# breadboard-long-with-header.net
KiCad netlist of a schematic drawn in EAGLE
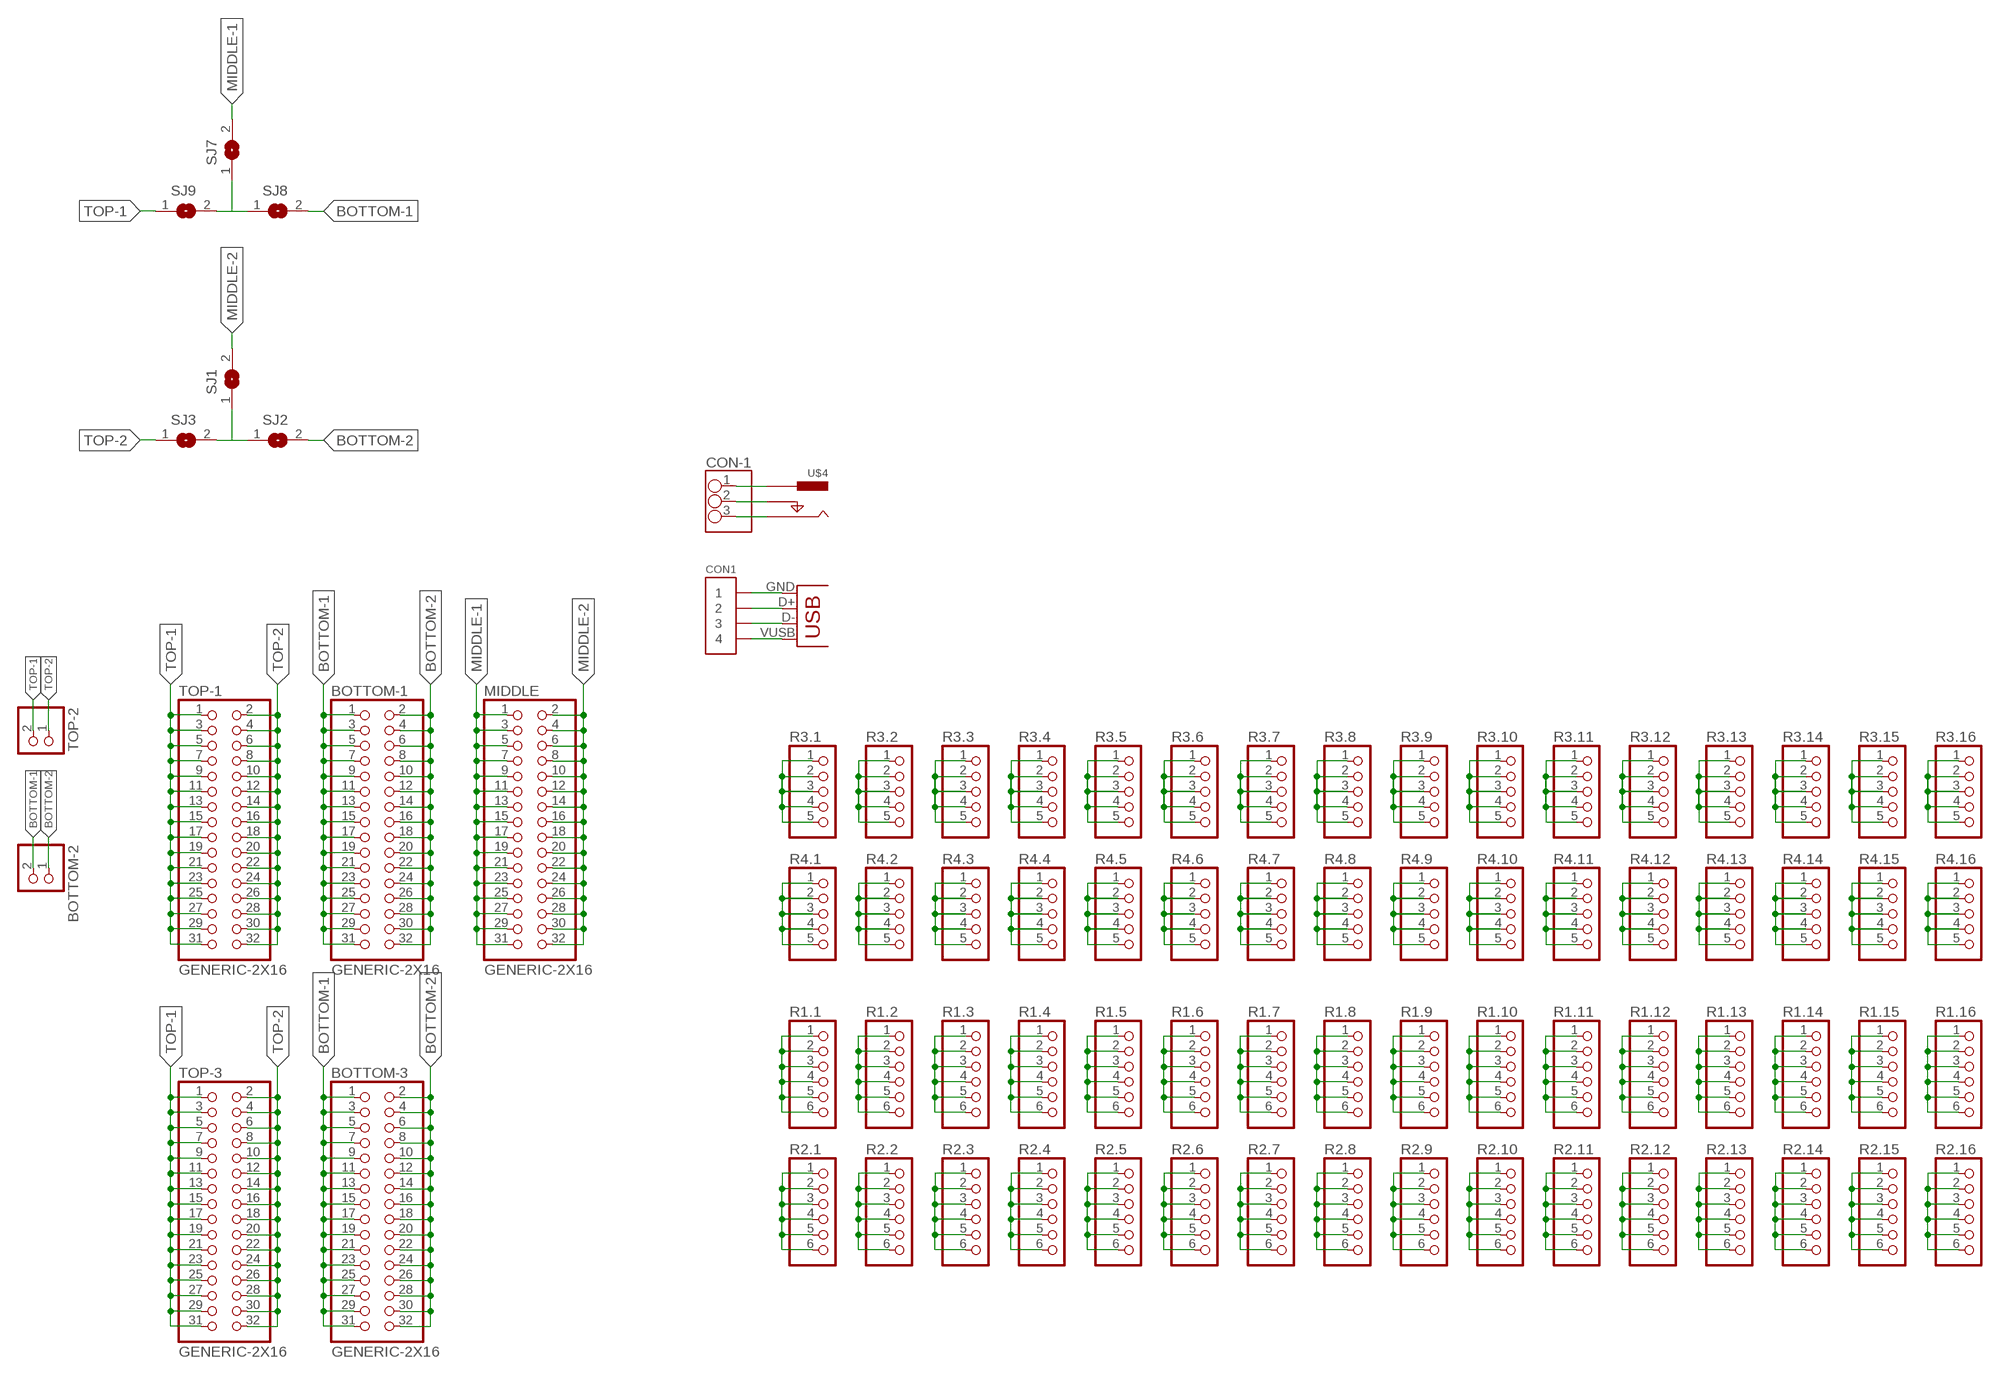
[diagram p0: schematic, sheet 1]

(export (version "E")
  (design (tool "Eeschema 10.0.6"))
  (components
    (comp (ref "BOTTOM-1")
      (value "GENERIC-2X16")
      (footprint "eagle-import:PINHEADER-100MIL-2X16-NOSILK")
      (libsource (lib "eagle-import") (part "GENERIC-2X16"))
    )
    (comp (ref "BOTTOM-2")
      (value "GENERIC-1X2")
      (footprint "eagle-import:PINHEADER-100MIL-1X2-NOSILK")
      (libsource (lib "eagle-import") (part "GENERIC-1X2"))
    )
    (comp (ref "BOTTOM-3")
      (value "GENERIC-2X16")
      (footprint "eagle-import:PINHEADER-100MIL-2X16-NOSILK")
      (libsource (lib "eagle-import") (part "GENERIC-2X16"))
    )
    (comp (ref "CON-1")
      (value "GENERIC-1X3")
      (footprint "eagle-import:PINHEADER-100MIL-1X3-NOSILK")
      (libsource (lib "eagle-import") (part "GENERIC-1X3"))
    )
    (comp (ref "CON1")
      (value "GENERIC-1X4STRAIGHT")
      (footprint "eagle-import:PINHEADER-100MIL-1X4-NOSILK")
      (libsource (lib "eagle-import") (part "GENERIC-1X4STRAIGHT"))
    )
    (comp (ref "MIDDLE")
      (value "GENERIC-2X16")
      (footprint "eagle-import:PINHEADER-100MIL-2X16-NOSILK")
      (libsource (lib "eagle-import") (part "GENERIC-2X16"))
    )
    (comp (ref "R1.1")
      (value "GENERIC-1X6")
      (footprint "eagle-import:PINHEADER-100MIL-1X6-NOSILK")
      (libsource (lib "eagle-import") (part "GENERIC-1X6"))
    )
    (comp (ref "R1.2")
      (value "GENERIC-1X6")
      (footprint "eagle-import:PINHEADER-100MIL-1X6-NOSILK")
      (libsource (lib "eagle-import") (part "GENERIC-1X6"))
    )
    (comp (ref "R1.3")
      (value "GENERIC-1X6")
      (footprint "eagle-import:PINHEADER-100MIL-1X6-NOSILK")
      (libsource (lib "eagle-import") (part "GENERIC-1X6"))
    )
    (comp (ref "R1.4")
      (value "GENERIC-1X6")
      (footprint "eagle-import:PINHEADER-100MIL-1X6-NOSILK")
      (libsource (lib "eagle-import") (part "GENERIC-1X6"))
    )
    (comp (ref "R1.5")
      (value "GENERIC-1X6")
      (footprint "eagle-import:PINHEADER-100MIL-1X6-NOSILK")
      (libsource (lib "eagle-import") (part "GENERIC-1X6"))
    )
    (comp (ref "R1.6")
      (value "GENERIC-1X6")
      (footprint "eagle-import:PINHEADER-100MIL-1X6-NOSILK")
      (libsource (lib "eagle-import") (part "GENERIC-1X6"))
    )
    (comp (ref "R1.7")
      (value "GENERIC-1X6")
      (footprint "eagle-import:PINHEADER-100MIL-1X6-NOSILK")
      (libsource (lib "eagle-import") (part "GENERIC-1X6"))
    )
    (comp (ref "R1.8")
      (value "GENERIC-1X6")
      (footprint "eagle-import:PINHEADER-100MIL-1X6-NOSILK")
      (libsource (lib "eagle-import") (part "GENERIC-1X6"))
    )
    (comp (ref "R1.9")
      (value "GENERIC-1X6")
      (footprint "eagle-import:PINHEADER-100MIL-1X6-NOSILK")
      (libsource (lib "eagle-import") (part "GENERIC-1X6"))
    )
    (comp (ref "R1.10")
      (value "GENERIC-1X6")
      (footprint "eagle-import:PINHEADER-100MIL-1X6-NOSILK")
      (libsource (lib "eagle-import") (part "GENERIC-1X6"))
    )
    (comp (ref "R1.11")
      (value "GENERIC-1X6")
      (footprint "eagle-import:PINHEADER-100MIL-1X6-NOSILK")
      (libsource (lib "eagle-import") (part "GENERIC-1X6"))
    )
    (comp (ref "R1.12")
      (value "GENERIC-1X6")
      (footprint "eagle-import:PINHEADER-100MIL-1X6-NOSILK")
      (libsource (lib "eagle-import") (part "GENERIC-1X6"))
    )
    (comp (ref "R1.13")
      (value "GENERIC-1X6")
      (footprint "eagle-import:PINHEADER-100MIL-1X6-NOSILK")
      (libsource (lib "eagle-import") (part "GENERIC-1X6"))
    )
    (comp (ref "R1.14")
      (value "GENERIC-1X6")
      (footprint "eagle-import:PINHEADER-100MIL-1X6-NOSILK")
      (libsource (lib "eagle-import") (part "GENERIC-1X6"))
    )
    (comp (ref "R1.15")
      (value "GENERIC-1X6")
      (footprint "eagle-import:PINHEADER-100MIL-1X6-NOSILK")
      (libsource (lib "eagle-import") (part "GENERIC-1X6"))
    )
    (comp (ref "R1.16")
      (value "GENERIC-1X6")
      (footprint "eagle-import:PINHEADER-100MIL-1X6-NOSILK")
      (libsource (lib "eagle-import") (part "GENERIC-1X6"))
    )
    (comp (ref "R2.1")
      (value "GENERIC-1X6")
      (footprint "eagle-import:PINHEADER-100MIL-1X6-NOSILK")
      (libsource (lib "eagle-import") (part "GENERIC-1X6"))
    )
    (comp (ref "R2.2")
      (value "GENERIC-1X6")
      (footprint "eagle-import:PINHEADER-100MIL-1X6-NOSILK")
      (libsource (lib "eagle-import") (part "GENERIC-1X6"))
    )
    (comp (ref "R2.3")
      (value "GENERIC-1X6")
      (footprint "eagle-import:PINHEADER-100MIL-1X6-NOSILK")
      (libsource (lib "eagle-import") (part "GENERIC-1X6"))
    )
    (comp (ref "R2.4")
      (value "GENERIC-1X6")
      (footprint "eagle-import:PINHEADER-100MIL-1X6-NOSILK")
      (libsource (lib "eagle-import") (part "GENERIC-1X6"))
    )
    (comp (ref "R2.5")
      (value "GENERIC-1X6")
      (footprint "eagle-import:PINHEADER-100MIL-1X6-NOSILK")
      (libsource (lib "eagle-import") (part "GENERIC-1X6"))
    )
    (comp (ref "R2.6")
      (value "GENERIC-1X6")
      (footprint "eagle-import:PINHEADER-100MIL-1X6-NOSILK")
      (libsource (lib "eagle-import") (part "GENERIC-1X6"))
    )
    (comp (ref "R2.7")
      (value "GENERIC-1X6")
      (footprint "eagle-import:PINHEADER-100MIL-1X6-NOSILK")
      (libsource (lib "eagle-import") (part "GENERIC-1X6"))
    )
    (comp (ref "R2.8")
      (value "GENERIC-1X6")
      (footprint "eagle-import:PINHEADER-100MIL-1X6-NOSILK")
      (libsource (lib "eagle-import") (part "GENERIC-1X6"))
    )
    (comp (ref "R2.9")
      (value "GENERIC-1X6")
      (footprint "eagle-import:PINHEADER-100MIL-1X6-NOSILK")
      (libsource (lib "eagle-import") (part "GENERIC-1X6"))
    )
    (comp (ref "R2.10")
      (value "GENERIC-1X6")
      (footprint "eagle-import:PINHEADER-100MIL-1X6-NOSILK")
      (libsource (lib "eagle-import") (part "GENERIC-1X6"))
    )
    (comp (ref "R2.11")
      (value "GENERIC-1X6")
      (footprint "eagle-import:PINHEADER-100MIL-1X6-NOSILK")
      (libsource (lib "eagle-import") (part "GENERIC-1X6"))
    )
    (comp (ref "R2.12")
      (value "GENERIC-1X6")
      (footprint "eagle-import:PINHEADER-100MIL-1X6-NOSILK")
      (libsource (lib "eagle-import") (part "GENERIC-1X6"))
    )
    (comp (ref "R2.13")
      (value "GENERIC-1X6")
      (footprint "eagle-import:PINHEADER-100MIL-1X6-NOSILK")
      (libsource (lib "eagle-import") (part "GENERIC-1X6"))
    )
    (comp (ref "R2.14")
      (value "GENERIC-1X6")
      (footprint "eagle-import:PINHEADER-100MIL-1X6-NOSILK")
      (libsource (lib "eagle-import") (part "GENERIC-1X6"))
    )
    (comp (ref "R2.15")
      (value "GENERIC-1X6")
      (footprint "eagle-import:PINHEADER-100MIL-1X6-NOSILK")
      (libsource (lib "eagle-import") (part "GENERIC-1X6"))
    )
    (comp (ref "R2.16")
      (value "GENERIC-1X6")
      (footprint "eagle-import:PINHEADER-100MIL-1X6-NOSILK")
      (libsource (lib "eagle-import") (part "GENERIC-1X6"))
    )
    (comp (ref "R3.1")
      (value "GENERIC-1X5")
      (footprint "eagle-import:PINHEADER-100MIL-1X5-NOSILK")
      (libsource (lib "eagle-import") (part "GENERIC-1X5"))
    )
    (comp (ref "R3.2")
      (value "GENERIC-1X5")
      (footprint "eagle-import:PINHEADER-100MIL-1X5-NOSILK")
      (libsource (lib "eagle-import") (part "GENERIC-1X5"))
    )
    (comp (ref "R3.3")
      (value "GENERIC-1X5")
      (footprint "eagle-import:PINHEADER-100MIL-1X5-NOSILK")
      (libsource (lib "eagle-import") (part "GENERIC-1X5"))
    )
    (comp (ref "R3.4")
      (value "GENERIC-1X5")
      (footprint "eagle-import:PINHEADER-100MIL-1X5-NOSILK")
      (libsource (lib "eagle-import") (part "GENERIC-1X5"))
    )
    (comp (ref "R3.5")
      (value "GENERIC-1X5")
      (footprint "eagle-import:PINHEADER-100MIL-1X5-NOSILK")
      (libsource (lib "eagle-import") (part "GENERIC-1X5"))
    )
    (comp (ref "R3.6")
      (value "GENERIC-1X5")
      (footprint "eagle-import:PINHEADER-100MIL-1X5-NOSILK")
      (libsource (lib "eagle-import") (part "GENERIC-1X5"))
    )
    (comp (ref "R3.7")
      (value "GENERIC-1X5")
      (footprint "eagle-import:PINHEADER-100MIL-1X5-NOSILK")
      (libsource (lib "eagle-import") (part "GENERIC-1X5"))
    )
    (comp (ref "R3.8")
      (value "GENERIC-1X5")
      (footprint "eagle-import:PINHEADER-100MIL-1X5-NOSILK")
      (libsource (lib "eagle-import") (part "GENERIC-1X5"))
    )
    (comp (ref "R3.9")
      (value "GENERIC-1X5")
      (footprint "eagle-import:PINHEADER-100MIL-1X5-NOSILK")
      (libsource (lib "eagle-import") (part "GENERIC-1X5"))
    )
    (comp (ref "R3.10")
      (value "GENERIC-1X5")
      (footprint "eagle-import:PINHEADER-100MIL-1X5-NOSILK")
      (libsource (lib "eagle-import") (part "GENERIC-1X5"))
    )
    (comp (ref "R3.11")
      (value "GENERIC-1X5")
      (footprint "eagle-import:PINHEADER-100MIL-1X5-NOSILK")
      (libsource (lib "eagle-import") (part "GENERIC-1X5"))
    )
    (comp (ref "R3.12")
      (value "GENERIC-1X5")
      (footprint "eagle-import:PINHEADER-100MIL-1X5-NOSILK")
      (libsource (lib "eagle-import") (part "GENERIC-1X5"))
    )
    (comp (ref "R3.13")
      (value "GENERIC-1X5")
      (footprint "eagle-import:PINHEADER-100MIL-1X5-NOSILK")
      (libsource (lib "eagle-import") (part "GENERIC-1X5"))
    )
    (comp (ref "R3.14")
      (value "GENERIC-1X5")
      (footprint "eagle-import:PINHEADER-100MIL-1X5-NOSILK")
      (libsource (lib "eagle-import") (part "GENERIC-1X5"))
    )
    (comp (ref "R3.15")
      (value "GENERIC-1X5")
      (footprint "eagle-import:PINHEADER-100MIL-1X5-NOSILK")
      (libsource (lib "eagle-import") (part "GENERIC-1X5"))
    )
    (comp (ref "R3.16")
      (value "GENERIC-1X5")
      (footprint "eagle-import:PINHEADER-100MIL-1X5-NOSILK")
      (libsource (lib "eagle-import") (part "GENERIC-1X5"))
    )
    (comp (ref "R4.1")
      (value "GENERIC-1X5")
      (footprint "eagle-import:PINHEADER-100MIL-1X5-NOSILK")
      (libsource (lib "eagle-import") (part "GENERIC-1X5"))
    )
    (comp (ref "R4.2")
      (value "GENERIC-1X5")
      (footprint "eagle-import:PINHEADER-100MIL-1X5-NOSILK")
      (libsource (lib "eagle-import") (part "GENERIC-1X5"))
    )
    (comp (ref "R4.3")
      (value "GENERIC-1X5")
      (footprint "eagle-import:PINHEADER-100MIL-1X5-NOSILK")
      (libsource (lib "eagle-import") (part "GENERIC-1X5"))
    )
    (comp (ref "R4.4")
      (value "GENERIC-1X5")
      (footprint "eagle-import:PINHEADER-100MIL-1X5-NOSILK")
      (libsource (lib "eagle-import") (part "GENERIC-1X5"))
    )
    (comp (ref "R4.5")
      (value "GENERIC-1X5")
      (footprint "eagle-import:PINHEADER-100MIL-1X5-NOSILK")
      (libsource (lib "eagle-import") (part "GENERIC-1X5"))
    )
    (comp (ref "R4.6")
      (value "GENERIC-1X5")
      (footprint "eagle-import:PINHEADER-100MIL-1X5-NOSILK")
      (libsource (lib "eagle-import") (part "GENERIC-1X5"))
    )
    (comp (ref "R4.7")
      (value "GENERIC-1X5")
      (footprint "eagle-import:PINHEADER-100MIL-1X5-NOSILK")
      (libsource (lib "eagle-import") (part "GENERIC-1X5"))
    )
    (comp (ref "R4.8")
      (value "GENERIC-1X5")
      (footprint "eagle-import:PINHEADER-100MIL-1X5-NOSILK")
      (libsource (lib "eagle-import") (part "GENERIC-1X5"))
    )
    (comp (ref "R4.9")
      (value "GENERIC-1X5")
      (footprint "eagle-import:PINHEADER-100MIL-1X5-NOSILK")
      (libsource (lib "eagle-import") (part "GENERIC-1X5"))
    )
    (comp (ref "R4.10")
      (value "GENERIC-1X5")
      (footprint "eagle-import:PINHEADER-100MIL-1X5-NOSILK")
      (libsource (lib "eagle-import") (part "GENERIC-1X5"))
    )
    (comp (ref "R4.11")
      (value "GENERIC-1X5")
      (footprint "eagle-import:PINHEADER-100MIL-1X5-NOSILK")
      (libsource (lib "eagle-import") (part "GENERIC-1X5"))
    )
    (comp (ref "R4.12")
      (value "GENERIC-1X5")
      (footprint "eagle-import:PINHEADER-100MIL-1X5-NOSILK")
      (libsource (lib "eagle-import") (part "GENERIC-1X5"))
    )
    (comp (ref "R4.13")
      (value "GENERIC-1X5")
      (footprint "eagle-import:PINHEADER-100MIL-1X5-NOSILK")
      (libsource (lib "eagle-import") (part "GENERIC-1X5"))
    )
    (comp (ref "R4.14")
      (value "GENERIC-1X5")
      (footprint "eagle-import:PINHEADER-100MIL-1X5-NOSILK")
      (libsource (lib "eagle-import") (part "GENERIC-1X5"))
    )
    (comp (ref "R4.15")
      (value "GENERIC-1X5")
      (footprint "eagle-import:PINHEADER-100MIL-1X5-NOSILK")
      (libsource (lib "eagle-import") (part "GENERIC-1X5"))
    )
    (comp (ref "R4.16")
      (value "GENERIC-1X5")
      (footprint "eagle-import:PINHEADER-100MIL-1X5-NOSILK")
      (libsource (lib "eagle-import") (part "GENERIC-1X5"))
    )
    (comp (ref "SJ1") (value "SJ") (footprint "eagle-import:SJ") (libsource (lib "eagle-import") (part "SJ")))
    (comp (ref "SJ2") (value "SJ") (footprint "eagle-import:SJ") (libsource (lib "eagle-import") (part "SJ")))
    (comp (ref "SJ3") (value "SJ") (footprint "eagle-import:SJ") (libsource (lib "eagle-import") (part "SJ")))
    (comp (ref "SJ7") (value "SJ") (footprint "eagle-import:SJ") (libsource (lib "eagle-import") (part "SJ")))
    (comp (ref "SJ8") (value "SJ") (footprint "eagle-import:SJ") (libsource (lib "eagle-import") (part "SJ")))
    (comp (ref "SJ9") (value "SJ") (footprint "eagle-import:SJ") (libsource (lib "eagle-import") (part "SJ")))
    (comp (ref "TOP-1")
      (value "GENERIC-2X16")
      (footprint "eagle-import:PINHEADER-100MIL-2X16-NOSILK")
      (libsource (lib "eagle-import") (part "GENERIC-2X16"))
    )
    (comp (ref "TOP-2")
      (value "GENERIC-1X2")
      (footprint "eagle-import:PINHEADER-100MIL-1X2-NOSILK")
      (libsource (lib "eagle-import") (part "GENERIC-1X2"))
    )
    (comp (ref "TOP-3")
      (value "GENERIC-2X16")
      (footprint "eagle-import:PINHEADER-100MIL-2X16-NOSILK")
      (libsource (lib "eagle-import") (part "GENERIC-2X16"))
    )
    (comp (ref "U$3")
      (value "USBMINI-HAND")
      (footprint "eagle-import:USB-MINI-B-HAND_EXTRA_LONG")
      (libsource (lib "eagle-import") (part "USBMINI-HAND"))
    )
    (comp (ref "U$4")
      (value "POWER-BARREL_JACKEBAY")
      (footprint "eagle-import:POWER-BARREL-2MM1-EBAY")
      (libsource (lib "eagle-import") (part "POWER-BARREL_JACKEBAY"))
    )
  )
  (nets
    (net (code "1") (name "BOTTOM-1") (class "Default")
      (node (ref "BOTTOM-1") (pin "1") (pinfunction "1_1") (pintype "passive"))
      (node (ref "BOTTOM-1") (pin "11") (pinfunction "11_11") (pintype "passive"))
      (node (ref "BOTTOM-1") (pin "13") (pinfunction "13_13") (pintype "passive"))
      (node (ref "BOTTOM-1") (pin "15") (pinfunction "15_15") (pintype "passive"))
      (node (ref "BOTTOM-1") (pin "17") (pinfunction "17_17") (pintype "passive"))
      (node (ref "BOTTOM-1") (pin "19") (pinfunction "19_19") (pintype "passive"))
      (node (ref "BOTTOM-1") (pin "21") (pinfunction "21_21") (pintype "passive"))
      (node (ref "BOTTOM-1") (pin "23") (pinfunction "23_23") (pintype "passive"))
      (node (ref "BOTTOM-1") (pin "25") (pinfunction "25_25") (pintype "passive"))
      (node (ref "BOTTOM-1") (pin "27") (pinfunction "27_27") (pintype "passive"))
      (node (ref "BOTTOM-1") (pin "29") (pinfunction "29_29") (pintype "passive"))
      (node (ref "BOTTOM-1") (pin "3") (pinfunction "3_3") (pintype "passive"))
      (node (ref "BOTTOM-1") (pin "31") (pinfunction "31_31") (pintype "passive"))
      (node (ref "BOTTOM-1") (pin "5") (pinfunction "5_5") (pintype "passive"))
      (node (ref "BOTTOM-1") (pin "7") (pinfunction "7_7") (pintype "passive"))
      (node (ref "BOTTOM-1") (pin "9") (pinfunction "9_9") (pintype "passive"))
      (node (ref "BOTTOM-2") (pin "2") (pinfunction "2_2") (pintype "passive"))
      (node (ref "BOTTOM-3") (pin "1") (pinfunction "1_1") (pintype "passive"))
      (node (ref "BOTTOM-3") (pin "11") (pinfunction "11_11") (pintype "passive"))
      (node (ref "BOTTOM-3") (pin "13") (pinfunction "13_13") (pintype "passive"))
      (node (ref "BOTTOM-3") (pin "15") (pinfunction "15_15") (pintype "passive"))
      (node (ref "BOTTOM-3") (pin "17") (pinfunction "17_17") (pintype "passive"))
      (node (ref "BOTTOM-3") (pin "19") (pinfunction "19_19") (pintype "passive"))
      (node (ref "BOTTOM-3") (pin "21") (pinfunction "21_21") (pintype "passive"))
      (node (ref "BOTTOM-3") (pin "23") (pinfunction "23_23") (pintype "passive"))
      (node (ref "BOTTOM-3") (pin "25") (pinfunction "25_25") (pintype "passive"))
      (node (ref "BOTTOM-3") (pin "27") (pinfunction "27_27") (pintype "passive"))
      (node (ref "BOTTOM-3") (pin "29") (pinfunction "29_29") (pintype "passive"))
      (node (ref "BOTTOM-3") (pin "3") (pinfunction "3_3") (pintype "passive"))
      (node (ref "BOTTOM-3") (pin "31") (pinfunction "31_31") (pintype "passive"))
      (node (ref "BOTTOM-3") (pin "5") (pinfunction "5_5") (pintype "passive"))
      (node (ref "BOTTOM-3") (pin "7") (pinfunction "7_7") (pintype "passive"))
      (node (ref "BOTTOM-3") (pin "9") (pinfunction "9_9") (pintype "passive"))
      (node (ref "SJ8") (pin "2") (pinfunction "2_2") (pintype "passive"))
    )
    (net (code "2") (name "BOTTOM-2") (class "Default")
      (node (ref "BOTTOM-1") (pin "10") (pinfunction "10_10") (pintype "passive"))
      (node (ref "BOTTOM-1") (pin "12") (pinfunction "12_12") (pintype "passive"))
      (node (ref "BOTTOM-1") (pin "14") (pinfunction "14_14") (pintype "passive"))
      (node (ref "BOTTOM-1") (pin "16") (pinfunction "16_16") (pintype "passive"))
      (node (ref "BOTTOM-1") (pin "18") (pinfunction "18_18") (pintype "passive"))
      (node (ref "BOTTOM-1") (pin "2") (pinfunction "2_2") (pintype "passive"))
      (node (ref "BOTTOM-1") (pin "20") (pinfunction "20_20") (pintype "passive"))
      (node (ref "BOTTOM-1") (pin "22") (pinfunction "22_22") (pintype "passive"))
      (node (ref "BOTTOM-1") (pin "24") (pinfunction "24_24") (pintype "passive"))
      (node (ref "BOTTOM-1") (pin "26") (pinfunction "26_26") (pintype "passive"))
      (node (ref "BOTTOM-1") (pin "28") (pinfunction "28_28") (pintype "passive"))
      (node (ref "BOTTOM-1") (pin "30") (pinfunction "30_30") (pintype "passive"))
      (node (ref "BOTTOM-1") (pin "32") (pinfunction "32_32") (pintype "passive"))
      (node (ref "BOTTOM-1") (pin "4") (pinfunction "4_4") (pintype "passive"))
      (node (ref "BOTTOM-1") (pin "6") (pinfunction "6_6") (pintype "passive"))
      (node (ref "BOTTOM-1") (pin "8") (pinfunction "8_8") (pintype "passive"))
      (node (ref "BOTTOM-2") (pin "1") (pinfunction "1_1") (pintype "passive"))
      (node (ref "BOTTOM-3") (pin "10") (pinfunction "10_10") (pintype "passive"))
      (node (ref "BOTTOM-3") (pin "12") (pinfunction "12_12") (pintype "passive"))
      (node (ref "BOTTOM-3") (pin "14") (pinfunction "14_14") (pintype "passive"))
      (node (ref "BOTTOM-3") (pin "16") (pinfunction "16_16") (pintype "passive"))
      (node (ref "BOTTOM-3") (pin "18") (pinfunction "18_18") (pintype "passive"))
      (node (ref "BOTTOM-3") (pin "2") (pinfunction "2_2") (pintype "passive"))
      (node (ref "BOTTOM-3") (pin "20") (pinfunction "20_20") (pintype "passive"))
      (node (ref "BOTTOM-3") (pin "22") (pinfunction "22_22") (pintype "passive"))
      (node (ref "BOTTOM-3") (pin "24") (pinfunction "24_24") (pintype "passive"))
      (node (ref "BOTTOM-3") (pin "26") (pinfunction "26_26") (pintype "passive"))
      (node (ref "BOTTOM-3") (pin "28") (pinfunction "28_28") (pintype "passive"))
      (node (ref "BOTTOM-3") (pin "30") (pinfunction "30_30") (pintype "passive"))
      (node (ref "BOTTOM-3") (pin "32") (pinfunction "32_32") (pintype "passive"))
      (node (ref "BOTTOM-3") (pin "4") (pinfunction "4_4") (pintype "passive"))
      (node (ref "BOTTOM-3") (pin "6") (pinfunction "6_6") (pintype "passive"))
      (node (ref "BOTTOM-3") (pin "8") (pinfunction "8_8") (pintype "passive"))
      (node (ref "SJ2") (pin "2") (pinfunction "2_2") (pintype "passive"))
    )
    (net (code "3") (name "MIDDLE-1") (class "Default")
      (node (ref "MIDDLE") (pin "1") (pinfunction "1_1") (pintype "passive"))
      (node (ref "MIDDLE") (pin "11") (pinfunction "11_11") (pintype "passive"))
      (node (ref "MIDDLE") (pin "13") (pinfunction "13_13") (pintype "passive"))
      (node (ref "MIDDLE") (pin "15") (pinfunction "15_15") (pintype "passive"))
      (node (ref "MIDDLE") (pin "17") (pinfunction "17_17") (pintype "passive"))
      (node (ref "MIDDLE") (pin "19") (pinfunction "19_19") (pintype "passive"))
      (node (ref "MIDDLE") (pin "21") (pinfunction "21_21") (pintype "passive"))
      (node (ref "MIDDLE") (pin "23") (pinfunction "23_23") (pintype "passive"))
      (node (ref "MIDDLE") (pin "25") (pinfunction "25_25") (pintype "passive"))
      (node (ref "MIDDLE") (pin "27") (pinfunction "27_27") (pintype "passive"))
      (node (ref "MIDDLE") (pin "29") (pinfunction "29_29") (pintype "passive"))
      (node (ref "MIDDLE") (pin "3") (pinfunction "3_3") (pintype "passive"))
      (node (ref "MIDDLE") (pin "31") (pinfunction "31_31") (pintype "passive"))
      (node (ref "MIDDLE") (pin "5") (pinfunction "5_5") (pintype "passive"))
      (node (ref "MIDDLE") (pin "7") (pinfunction "7_7") (pintype "passive"))
      (node (ref "MIDDLE") (pin "9") (pinfunction "9_9") (pintype "passive"))
      (node (ref "SJ7") (pin "2") (pinfunction "2_2") (pintype "passive"))
    )
    (net (code "4") (name "MIDDLE-2") (class "Default")
      (node (ref "MIDDLE") (pin "10") (pinfunction "10_10") (pintype "passive"))
      (node (ref "MIDDLE") (pin "12") (pinfunction "12_12") (pintype "passive"))
      (node (ref "MIDDLE") (pin "14") (pinfunction "14_14") (pintype "passive"))
      (node (ref "MIDDLE") (pin "16") (pinfunction "16_16") (pintype "passive"))
      (node (ref "MIDDLE") (pin "18") (pinfunction "18_18") (pintype "passive"))
      (node (ref "MIDDLE") (pin "2") (pinfunction "2_2") (pintype "passive"))
      (node (ref "MIDDLE") (pin "20") (pinfunction "20_20") (pintype "passive"))
      (node (ref "MIDDLE") (pin "22") (pinfunction "22_22") (pintype "passive"))
      (node (ref "MIDDLE") (pin "24") (pinfunction "24_24") (pintype "passive"))
      (node (ref "MIDDLE") (pin "26") (pinfunction "26_26") (pintype "passive"))
      (node (ref "MIDDLE") (pin "28") (pinfunction "28_28") (pintype "passive"))
      (node (ref "MIDDLE") (pin "30") (pinfunction "30_30") (pintype "passive"))
      (node (ref "MIDDLE") (pin "32") (pinfunction "32_32") (pintype "passive"))
      (node (ref "MIDDLE") (pin "4") (pinfunction "4_4") (pintype "passive"))
      (node (ref "MIDDLE") (pin "6") (pinfunction "6_6") (pintype "passive"))
      (node (ref "MIDDLE") (pin "8") (pinfunction "8_8") (pintype "passive"))
      (node (ref "SJ1") (pin "2") (pinfunction "2_2") (pintype "passive"))
    )
    (net (code "5") (name "Net-(CON1-Pad1)") (class "Default")
      (node (ref "CON1") (pin "1") (pinfunction "1_1") (pintype "bidirectional"))
      (node (ref "U$3") (pin "GND") (pinfunction "GND_GND") (pintype "bidirectional"))
    )
    (net (code "6") (name "Net-(CON1-Pad2)") (class "Default")
      (node (ref "CON1") (pin "2") (pinfunction "2_2") (pintype "bidirectional"))
      (node (ref "U$3") (pin "D+") (pinfunction "D+_D+") (pintype "bidirectional"))
    )
    (net (code "7") (name "Net-(CON1-Pad3)") (class "Default")
      (node (ref "CON1") (pin "3") (pinfunction "3_3") (pintype "bidirectional"))
      (node (ref "U$3") (pin "D-") (pinfunction "D-_D-") (pintype "bidirectional"))
    )
    (net (code "8") (name "Net-(R1.1-Pad1)") (class "Default")
      (node (ref "R1.1") (pin "1") (pinfunction "1_1") (pintype "passive"))
      (node (ref "R1.1") (pin "2") (pinfunction "2_2") (pintype "passive"))
      (node (ref "R1.1") (pin "3") (pinfunction "3_3") (pintype "passive"))
      (node (ref "R1.1") (pin "4") (pinfunction "4_4") (pintype "passive"))
      (node (ref "R1.1") (pin "5") (pinfunction "5_5") (pintype "passive"))
      (node (ref "R1.1") (pin "6") (pinfunction "6_6") (pintype "passive"))
    )
    (net (code "9") (name "Net-(R1.2-Pad1)") (class "Default")
      (node (ref "R1.2") (pin "1") (pinfunction "1_1") (pintype "passive"))
      (node (ref "R1.2") (pin "2") (pinfunction "2_2") (pintype "passive"))
      (node (ref "R1.2") (pin "3") (pinfunction "3_3") (pintype "passive"))
      (node (ref "R1.2") (pin "4") (pinfunction "4_4") (pintype "passive"))
      (node (ref "R1.2") (pin "5") (pinfunction "5_5") (pintype "passive"))
      (node (ref "R1.2") (pin "6") (pinfunction "6_6") (pintype "passive"))
    )
    (net (code "10") (name "Net-(R1.3-Pad1)") (class "Default")
      (node (ref "R1.3") (pin "1") (pinfunction "1_1") (pintype "passive"))
      (node (ref "R1.3") (pin "2") (pinfunction "2_2") (pintype "passive"))
      (node (ref "R1.3") (pin "3") (pinfunction "3_3") (pintype "passive"))
      (node (ref "R1.3") (pin "4") (pinfunction "4_4") (pintype "passive"))
      (node (ref "R1.3") (pin "5") (pinfunction "5_5") (pintype "passive"))
      (node (ref "R1.3") (pin "6") (pinfunction "6_6") (pintype "passive"))
    )
    (net (code "11") (name "Net-(R1.4-Pad1)") (class "Default")
      (node (ref "R1.4") (pin "1") (pinfunction "1_1") (pintype "passive"))
      (node (ref "R1.4") (pin "2") (pinfunction "2_2") (pintype "passive"))
      (node (ref "R1.4") (pin "3") (pinfunction "3_3") (pintype "passive"))
      (node (ref "R1.4") (pin "4") (pinfunction "4_4") (pintype "passive"))
      (node (ref "R1.4") (pin "5") (pinfunction "5_5") (pintype "passive"))
      (node (ref "R1.4") (pin "6") (pinfunction "6_6") (pintype "passive"))
    )
    (net (code "12") (name "Net-(R1.5-Pad1)") (class "Default")
      (node (ref "R1.5") (pin "1") (pinfunction "1_1") (pintype "passive"))
      (node (ref "R1.5") (pin "2") (pinfunction "2_2") (pintype "passive"))
      (node (ref "R1.5") (pin "3") (pinfunction "3_3") (pintype "passive"))
      (node (ref "R1.5") (pin "4") (pinfunction "4_4") (pintype "passive"))
      (node (ref "R1.5") (pin "5") (pinfunction "5_5") (pintype "passive"))
      (node (ref "R1.5") (pin "6") (pinfunction "6_6") (pintype "passive"))
    )
    (net (code "13") (name "Net-(R1.6-Pad1)") (class "Default")
      (node (ref "R1.6") (pin "1") (pinfunction "1_1") (pintype "passive"))
      (node (ref "R1.6") (pin "2") (pinfunction "2_2") (pintype "passive"))
      (node (ref "R1.6") (pin "3") (pinfunction "3_3") (pintype "passive"))
      (node (ref "R1.6") (pin "4") (pinfunction "4_4") (pintype "passive"))
      (node (ref "R1.6") (pin "5") (pinfunction "5_5") (pintype "passive"))
      (node (ref "R1.6") (pin "6") (pinfunction "6_6") (pintype "passive"))
    )
    (net (code "14") (name "Net-(R1.7-Pad1)") (class "Default")
      (node (ref "R1.7") (pin "1") (pinfunction "1_1") (pintype "passive"))
      (node (ref "R1.7") (pin "2") (pinfunction "2_2") (pintype "passive"))
      (node (ref "R1.7") (pin "3") (pinfunction "3_3") (pintype "passive"))
      (node (ref "R1.7") (pin "4") (pinfunction "4_4") (pintype "passive"))
      (node (ref "R1.7") (pin "5") (pinfunction "5_5") (pintype "passive"))
      (node (ref "R1.7") (pin "6") (pinfunction "6_6") (pintype "passive"))
    )
    (net (code "15") (name "Net-(R1.8-Pad1)") (class "Default")
      (node (ref "R1.8") (pin "1") (pinfunction "1_1") (pintype "passive"))
      (node (ref "R1.8") (pin "2") (pinfunction "2_2") (pintype "passive"))
      (node (ref "R1.8") (pin "3") (pinfunction "3_3") (pintype "passive"))
      (node (ref "R1.8") (pin "4") (pinfunction "4_4") (pintype "passive"))
      (node (ref "R1.8") (pin "5") (pinfunction "5_5") (pintype "passive"))
      (node (ref "R1.8") (pin "6") (pinfunction "6_6") (pintype "passive"))
    )
    (net (code "16") (name "Net-(R1.9-Pad1)") (class "Default")
      (node (ref "R1.9") (pin "1") (pinfunction "1_1") (pintype "passive"))
      (node (ref "R1.9") (pin "2") (pinfunction "2_2") (pintype "passive"))
      (node (ref "R1.9") (pin "3") (pinfunction "3_3") (pintype "passive"))
      (node (ref "R1.9") (pin "4") (pinfunction "4_4") (pintype "passive"))
      (node (ref "R1.9") (pin "5") (pinfunction "5_5") (pintype "passive"))
      (node (ref "R1.9") (pin "6") (pinfunction "6_6") (pintype "passive"))
    )
    (net (code "17") (name "Net-(R1.10-Pad1)") (class "Default")
      (node (ref "R1.10") (pin "1") (pinfunction "1_1") (pintype "passive"))
      (node (ref "R1.10") (pin "2") (pinfunction "2_2") (pintype "passive"))
      (node (ref "R1.10") (pin "3") (pinfunction "3_3") (pintype "passive"))
      (node (ref "R1.10") (pin "4") (pinfunction "4_4") (pintype "passive"))
      (node (ref "R1.10") (pin "5") (pinfunction "5_5") (pintype "passive"))
      (node (ref "R1.10") (pin "6") (pinfunction "6_6") (pintype "passive"))
    )
    (net (code "18") (name "Net-(R1.11-Pad1)") (class "Default")
      (node (ref "R1.11") (pin "1") (pinfunction "1_1") (pintype "passive"))
      (node (ref "R1.11") (pin "2") (pinfunction "2_2") (pintype "passive"))
      (node (ref "R1.11") (pin "3") (pinfunction "3_3") (pintype "passive"))
      (node (ref "R1.11") (pin "4") (pinfunction "4_4") (pintype "passive"))
      (node (ref "R1.11") (pin "5") (pinfunction "5_5") (pintype "passive"))
      (node (ref "R1.11") (pin "6") (pinfunction "6_6") (pintype "passive"))
    )
    (net (code "19") (name "Net-(R1.12-Pad1)") (class "Default")
      (node (ref "R1.12") (pin "1") (pinfunction "1_1") (pintype "passive"))
      (node (ref "R1.12") (pin "2") (pinfunction "2_2") (pintype "passive"))
      (node (ref "R1.12") (pin "3") (pinfunction "3_3") (pintype "passive"))
      (node (ref "R1.12") (pin "4") (pinfunction "4_4") (pintype "passive"))
      (node (ref "R1.12") (pin "5") (pinfunction "5_5") (pintype "passive"))
      (node (ref "R1.12") (pin "6") (pinfunction "6_6") (pintype "passive"))
    )
    (net (code "20") (name "Net-(R1.13-Pad1)") (class "Default")
      (node (ref "R1.13") (pin "1") (pinfunction "1_1") (pintype "passive"))
      (node (ref "R1.13") (pin "2") (pinfunction "2_2") (pintype "passive"))
      (node (ref "R1.13") (pin "3") (pinfunction "3_3") (pintype "passive"))
      (node (ref "R1.13") (pin "4") (pinfunction "4_4") (pintype "passive"))
      (node (ref "R1.13") (pin "5") (pinfunction "5_5") (pintype "passive"))
      (node (ref "R1.13") (pin "6") (pinfunction "6_6") (pintype "passive"))
    )
    (net (code "21") (name "Net-(R1.14-Pad1)") (class "Default")
      (node (ref "R1.14") (pin "1") (pinfunction "1_1") (pintype "passive"))
      (node (ref "R1.14") (pin "2") (pinfunction "2_2") (pintype "passive"))
      (node (ref "R1.14") (pin "3") (pinfunction "3_3") (pintype "passive"))
      (node (ref "R1.14") (pin "4") (pinfunction "4_4") (pintype "passive"))
      (node (ref "R1.14") (pin "5") (pinfunction "5_5") (pintype "passive"))
      (node (ref "R1.14") (pin "6") (pinfunction "6_6") (pintype "passive"))
    )
    (net (code "22") (name "Net-(R1.15-Pad1)") (class "Default")
      (node (ref "R1.15") (pin "1") (pinfunction "1_1") (pintype "passive"))
      (node (ref "R1.15") (pin "2") (pinfunction "2_2") (pintype "passive"))
      (node (ref "R1.15") (pin "3") (pinfunction "3_3") (pintype "passive"))
      (node (ref "R1.15") (pin "4") (pinfunction "4_4") (pintype "passive"))
      (node (ref "R1.15") (pin "5") (pinfunction "5_5") (pintype "passive"))
      (node (ref "R1.15") (pin "6") (pinfunction "6_6") (pintype "passive"))
    )
    (net (code "23") (name "Net-(R1.16-Pad1)") (class "Default")
      (node (ref "R1.16") (pin "1") (pinfunction "1_1") (pintype "passive"))
      (node (ref "R1.16") (pin "2") (pinfunction "2_2") (pintype "passive"))
      (node (ref "R1.16") (pin "3") (pinfunction "3_3") (pintype "passive"))
      (node (ref "R1.16") (pin "4") (pinfunction "4_4") (pintype "passive"))
      (node (ref "R1.16") (pin "5") (pinfunction "5_5") (pintype "passive"))
      (node (ref "R1.16") (pin "6") (pinfunction "6_6") (pintype "passive"))
    )
    (net (code "24") (name "Net-(R2.1-Pad1)") (class "Default")
      (node (ref "R2.1") (pin "1") (pinfunction "1_1") (pintype "passive"))
      (node (ref "R2.1") (pin "2") (pinfunction "2_2") (pintype "passive"))
      (node (ref "R2.1") (pin "3") (pinfunction "3_3") (pintype "passive"))
      (node (ref "R2.1") (pin "4") (pinfunction "4_4") (pintype "passive"))
      (node (ref "R2.1") (pin "5") (pinfunction "5_5") (pintype "passive"))
      (node (ref "R2.1") (pin "6") (pinfunction "6_6") (pintype "passive"))
    )
    (net (code "25") (name "Net-(R2.2-Pad1)") (class "Default")
      (node (ref "R2.2") (pin "1") (pinfunction "1_1") (pintype "passive"))
      (node (ref "R2.2") (pin "2") (pinfunction "2_2") (pintype "passive"))
      (node (ref "R2.2") (pin "3") (pinfunction "3_3") (pintype "passive"))
      (node (ref "R2.2") (pin "4") (pinfunction "4_4") (pintype "passive"))
      (node (ref "R2.2") (pin "5") (pinfunction "5_5") (pintype "passive"))
      (node (ref "R2.2") (pin "6") (pinfunction "6_6") (pintype "passive"))
    )
    (net (code "26") (name "Net-(R2.3-Pad1)") (class "Default")
      (node (ref "R2.3") (pin "1") (pinfunction "1_1") (pintype "passive"))
      (node (ref "R2.3") (pin "2") (pinfunction "2_2") (pintype "passive"))
      (node (ref "R2.3") (pin "3") (pinfunction "3_3") (pintype "passive"))
      (node (ref "R2.3") (pin "4") (pinfunction "4_4") (pintype "passive"))
      (node (ref "R2.3") (pin "5") (pinfunction "5_5") (pintype "passive"))
      (node (ref "R2.3") (pin "6") (pinfunction "6_6") (pintype "passive"))
    )
    (net (code "27") (name "Net-(R2.4-Pad1)") (class "Default")
      (node (ref "R2.4") (pin "1") (pinfunction "1_1") (pintype "passive"))
      (node (ref "R2.4") (pin "2") (pinfunction "2_2") (pintype "passive"))
      (node (ref "R2.4") (pin "3") (pinfunction "3_3") (pintype "passive"))
      (node (ref "R2.4") (pin "4") (pinfunction "4_4") (pintype "passive"))
      (node (ref "R2.4") (pin "5") (pinfunction "5_5") (pintype "passive"))
      (node (ref "R2.4") (pin "6") (pinfunction "6_6") (pintype "passive"))
    )
    (net (code "28") (name "Net-(R2.5-Pad1)") (class "Default")
      (node (ref "R2.5") (pin "1") (pinfunction "1_1") (pintype "passive"))
      (node (ref "R2.5") (pin "2") (pinfunction "2_2") (pintype "passive"))
      (node (ref "R2.5") (pin "3") (pinfunction "3_3") (pintype "passive"))
      (node (ref "R2.5") (pin "4") (pinfunction "4_4") (pintype "passive"))
      (node (ref "R2.5") (pin "5") (pinfunction "5_5") (pintype "passive"))
      (node (ref "R2.5") (pin "6") (pinfunction "6_6") (pintype "passive"))
    )
    (net (code "29") (name "Net-(R2.6-Pad1)") (class "Default")
      (node (ref "R2.6") (pin "1") (pinfunction "1_1") (pintype "passive"))
      (node (ref "R2.6") (pin "2") (pinfunction "2_2") (pintype "passive"))
      (node (ref "R2.6") (pin "3") (pinfunction "3_3") (pintype "passive"))
      (node (ref "R2.6") (pin "4") (pinfunction "4_4") (pintype "passive"))
      (node (ref "R2.6") (pin "5") (pinfunction "5_5") (pintype "passive"))
      (node (ref "R2.6") (pin "6") (pinfunction "6_6") (pintype "passive"))
    )
    (net (code "30") (name "Net-(R2.7-Pad1)") (class "Default")
      (node (ref "R2.7") (pin "1") (pinfunction "1_1") (pintype "passive"))
      (node (ref "R2.7") (pin "2") (pinfunction "2_2") (pintype "passive"))
      (node (ref "R2.7") (pin "3") (pinfunction "3_3") (pintype "passive"))
      (node (ref "R2.7") (pin "4") (pinfunction "4_4") (pintype "passive"))
      (node (ref "R2.7") (pin "5") (pinfunction "5_5") (pintype "passive"))
      (node (ref "R2.7") (pin "6") (pinfunction "6_6") (pintype "passive"))
    )
    (net (code "31") (name "Net-(R2.8-Pad1)") (class "Default")
      (node (ref "R2.8") (pin "1") (pinfunction "1_1") (pintype "passive"))
      (node (ref "R2.8") (pin "2") (pinfunction "2_2") (pintype "passive"))
      (node (ref "R2.8") (pin "3") (pinfunction "3_3") (pintype "passive"))
      (node (ref "R2.8") (pin "4") (pinfunction "4_4") (pintype "passive"))
      (node (ref "R2.8") (pin "5") (pinfunction "5_5") (pintype "passive"))
      (node (ref "R2.8") (pin "6") (pinfunction "6_6") (pintype "passive"))
    )
    (net (code "32") (name "Net-(R2.9-Pad1)") (class "Default")
      (node (ref "R2.9") (pin "1") (pinfunction "1_1") (pintype "passive"))
      (node (ref "R2.9") (pin "2") (pinfunction "2_2") (pintype "passive"))
      (node (ref "R2.9") (pin "3") (pinfunction "3_3") (pintype "passive"))
      (node (ref "R2.9") (pin "4") (pinfunction "4_4") (pintype "passive"))
      (node (ref "R2.9") (pin "5") (pinfunction "5_5") (pintype "passive"))
      (node (ref "R2.9") (pin "6") (pinfunction "6_6") (pintype "passive"))
    )
    (net (code "33") (name "Net-(R2.10-Pad1)") (class "Default")
      (node (ref "R2.10") (pin "1") (pinfunction "1_1") (pintype "passive"))
      (node (ref "R2.10") (pin "2") (pinfunction "2_2") (pintype "passive"))
      (node (ref "R2.10") (pin "3") (pinfunction "3_3") (pintype "passive"))
      (node (ref "R2.10") (pin "4") (pinfunction "4_4") (pintype "passive"))
      (node (ref "R2.10") (pin "5") (pinfunction "5_5") (pintype "passive"))
      (node (ref "R2.10") (pin "6") (pinfunction "6_6") (pintype "passive"))
    )
    (net (code "34") (name "Net-(R2.11-Pad1)") (class "Default")
      (node (ref "R2.11") (pin "1") (pinfunction "1_1") (pintype "passive"))
      (node (ref "R2.11") (pin "2") (pinfunction "2_2") (pintype "passive"))
      (node (ref "R2.11") (pin "3") (pinfunction "3_3") (pintype "passive"))
      (node (ref "R2.11") (pin "4") (pinfunction "4_4") (pintype "passive"))
      (node (ref "R2.11") (pin "5") (pinfunction "5_5") (pintype "passive"))
      (node (ref "R2.11") (pin "6") (pinfunction "6_6") (pintype "passive"))
    )
    (net (code "35") (name "Net-(R2.12-Pad1)") (class "Default")
      (node (ref "R2.12") (pin "1") (pinfunction "1_1") (pintype "passive"))
      (node (ref "R2.12") (pin "2") (pinfunction "2_2") (pintype "passive"))
      (node (ref "R2.12") (pin "3") (pinfunction "3_3") (pintype "passive"))
      (node (ref "R2.12") (pin "4") (pinfunction "4_4") (pintype "passive"))
      (node (ref "R2.12") (pin "5") (pinfunction "5_5") (pintype "passive"))
      (node (ref "R2.12") (pin "6") (pinfunction "6_6") (pintype "passive"))
    )
    (net (code "36") (name "Net-(R2.13-Pad1)") (class "Default")
      (node (ref "R2.13") (pin "1") (pinfunction "1_1") (pintype "passive"))
      (node (ref "R2.13") (pin "2") (pinfunction "2_2") (pintype "passive"))
      (node (ref "R2.13") (pin "3") (pinfunction "3_3") (pintype "passive"))
      (node (ref "R2.13") (pin "4") (pinfunction "4_4") (pintype "passive"))
      (node (ref "R2.13") (pin "5") (pinfunction "5_5") (pintype "passive"))
      (node (ref "R2.13") (pin "6") (pinfunction "6_6") (pintype "passive"))
    )
    (net (code "37") (name "Net-(R2.14-Pad1)") (class "Default")
      (node (ref "R2.14") (pin "1") (pinfunction "1_1") (pintype "passive"))
      (node (ref "R2.14") (pin "2") (pinfunction "2_2") (pintype "passive"))
      (node (ref "R2.14") (pin "3") (pinfunction "3_3") (pintype "passive"))
      (node (ref "R2.14") (pin "4") (pinfunction "4_4") (pintype "passive"))
      (node (ref "R2.14") (pin "5") (pinfunction "5_5") (pintype "passive"))
      (node (ref "R2.14") (pin "6") (pinfunction "6_6") (pintype "passive"))
    )
    (net (code "38") (name "Net-(R2.15-Pad1)") (class "Default")
      (node (ref "R2.15") (pin "1") (pinfunction "1_1") (pintype "passive"))
      (node (ref "R2.15") (pin "2") (pinfunction "2_2") (pintype "passive"))
      (node (ref "R2.15") (pin "3") (pinfunction "3_3") (pintype "passive"))
      (node (ref "R2.15") (pin "4") (pinfunction "4_4") (pintype "passive"))
      (node (ref "R2.15") (pin "5") (pinfunction "5_5") (pintype "passive"))
      (node (ref "R2.15") (pin "6") (pinfunction "6_6") (pintype "passive"))
    )
    (net (code "39") (name "Net-(R2.16-Pad1)") (class "Default")
      (node (ref "R2.16") (pin "1") (pinfunction "1_1") (pintype "passive"))
      (node (ref "R2.16") (pin "2") (pinfunction "2_2") (pintype "passive"))
      (node (ref "R2.16") (pin "3") (pinfunction "3_3") (pintype "passive"))
      (node (ref "R2.16") (pin "4") (pinfunction "4_4") (pintype "passive"))
      (node (ref "R2.16") (pin "5") (pinfunction "5_5") (pintype "passive"))
      (node (ref "R2.16") (pin "6") (pinfunction "6_6") (pintype "passive"))
    )
    (net (code "40") (name "Net-(R3.1-Pad1)") (class "Default")
      (node (ref "R3.1") (pin "1") (pinfunction "1_1") (pintype "passive"))
      (node (ref "R3.1") (pin "2") (pinfunction "2_2") (pintype "passive"))
      (node (ref "R3.1") (pin "3") (pinfunction "3_3") (pintype "passive"))
      (node (ref "R3.1") (pin "4") (pinfunction "4_4") (pintype "passive"))
      (node (ref "R3.1") (pin "5") (pinfunction "5_5") (pintype "passive"))
    )
    (net (code "41") (name "Net-(R3.2-Pad1)") (class "Default")
      (node (ref "R3.2") (pin "1") (pinfunction "1_1") (pintype "passive"))
      (node (ref "R3.2") (pin "2") (pinfunction "2_2") (pintype "passive"))
      (node (ref "R3.2") (pin "3") (pinfunction "3_3") (pintype "passive"))
      (node (ref "R3.2") (pin "4") (pinfunction "4_4") (pintype "passive"))
      (node (ref "R3.2") (pin "5") (pinfunction "5_5") (pintype "passive"))
    )
    (net (code "42") (name "Net-(R3.3-Pad1)") (class "Default")
      (node (ref "R3.3") (pin "1") (pinfunction "1_1") (pintype "passive"))
      (node (ref "R3.3") (pin "2") (pinfunction "2_2") (pintype "passive"))
      (node (ref "R3.3") (pin "3") (pinfunction "3_3") (pintype "passive"))
      (node (ref "R3.3") (pin "4") (pinfunction "4_4") (pintype "passive"))
      (node (ref "R3.3") (pin "5") (pinfunction "5_5") (pintype "passive"))
    )
    (net (code "43") (name "Net-(R3.4-Pad1)") (class "Default")
      (node (ref "R3.4") (pin "1") (pinfunction "1_1") (pintype "passive"))
      (node (ref "R3.4") (pin "2") (pinfunction "2_2") (pintype "passive"))
      (node (ref "R3.4") (pin "3") (pinfunction "3_3") (pintype "passive"))
      (node (ref "R3.4") (pin "4") (pinfunction "4_4") (pintype "passive"))
      (node (ref "R3.4") (pin "5") (pinfunction "5_5") (pintype "passive"))
    )
    (net (code "44") (name "Net-(R3.5-Pad1)") (class "Default")
      (node (ref "R3.5") (pin "1") (pinfunction "1_1") (pintype "passive"))
      (node (ref "R3.5") (pin "2") (pinfunction "2_2") (pintype "passive"))
      (node (ref "R3.5") (pin "3") (pinfunction "3_3") (pintype "passive"))
      (node (ref "R3.5") (pin "4") (pinfunction "4_4") (pintype "passive"))
      (node (ref "R3.5") (pin "5") (pinfunction "5_5") (pintype "passive"))
    )
    (net (code "45") (name "Net-(R3.6-Pad1)") (class "Default")
      (node (ref "R3.6") (pin "1") (pinfunction "1_1") (pintype "passive"))
      (node (ref "R3.6") (pin "2") (pinfunction "2_2") (pintype "passive"))
      (node (ref "R3.6") (pin "3") (pinfunction "3_3") (pintype "passive"))
      (node (ref "R3.6") (pin "4") (pinfunction "4_4") (pintype "passive"))
      (node (ref "R3.6") (pin "5") (pinfunction "5_5") (pintype "passive"))
    )
    (net (code "46") (name "Net-(R3.7-Pad1)") (class "Default")
      (node (ref "R3.7") (pin "1") (pinfunction "1_1") (pintype "passive"))
      (node (ref "R3.7") (pin "2") (pinfunction "2_2") (pintype "passive"))
      (node (ref "R3.7") (pin "3") (pinfunction "3_3") (pintype "passive"))
      (node (ref "R3.7") (pin "4") (pinfunction "4_4") (pintype "passive"))
      (node (ref "R3.7") (pin "5") (pinfunction "5_5") (pintype "passive"))
    )
    (net (code "47") (name "Net-(R3.8-Pad1)") (class "Default")
      (node (ref "R3.8") (pin "1") (pinfunction "1_1") (pintype "passive"))
      (node (ref "R3.8") (pin "2") (pinfunction "2_2") (pintype "passive"))
      (node (ref "R3.8") (pin "3") (pinfunction "3_3") (pintype "passive"))
      (node (ref "R3.8") (pin "4") (pinfunction "4_4") (pintype "passive"))
      (node (ref "R3.8") (pin "5") (pinfunction "5_5") (pintype "passive"))
    )
    (net (code "48") (name "Net-(R3.9-Pad1)") (class "Default")
      (node (ref "R3.9") (pin "1") (pinfunction "1_1") (pintype "passive"))
      (node (ref "R3.9") (pin "2") (pinfunction "2_2") (pintype "passive"))
      (node (ref "R3.9") (pin "3") (pinfunction "3_3") (pintype "passive"))
      (node (ref "R3.9") (pin "4") (pinfunction "4_4") (pintype "passive"))
      (node (ref "R3.9") (pin "5") (pinfunction "5_5") (pintype "passive"))
    )
    (net (code "49") (name "Net-(R3.10-Pad1)") (class "Default")
      (node (ref "R3.10") (pin "1") (pinfunction "1_1") (pintype "passive"))
      (node (ref "R3.10") (pin "2") (pinfunction "2_2") (pintype "passive"))
      (node (ref "R3.10") (pin "3") (pinfunction "3_3") (pintype "passive"))
      (node (ref "R3.10") (pin "4") (pinfunction "4_4") (pintype "passive"))
      (node (ref "R3.10") (pin "5") (pinfunction "5_5") (pintype "passive"))
    )
    (net (code "50") (name "Net-(R3.11-Pad1)") (class "Default")
      (node (ref "R3.11") (pin "1") (pinfunction "1_1") (pintype "passive"))
      (node (ref "R3.11") (pin "2") (pinfunction "2_2") (pintype "passive"))
      (node (ref "R3.11") (pin "3") (pinfunction "3_3") (pintype "passive"))
      (node (ref "R3.11") (pin "4") (pinfunction "4_4") (pintype "passive"))
      (node (ref "R3.11") (pin "5") (pinfunction "5_5") (pintype "passive"))
    )
    (net (code "51") (name "Net-(R3.12-Pad1)") (class "Default")
      (node (ref "R3.12") (pin "1") (pinfunction "1_1") (pintype "passive"))
      (node (ref "R3.12") (pin "2") (pinfunction "2_2") (pintype "passive"))
      (node (ref "R3.12") (pin "3") (pinfunction "3_3") (pintype "passive"))
      (node (ref "R3.12") (pin "4") (pinfunction "4_4") (pintype "passive"))
      (node (ref "R3.12") (pin "5") (pinfunction "5_5") (pintype "passive"))
    )
    (net (code "52") (name "Net-(R3.13-Pad1)") (class "Default")
      (node (ref "R3.13") (pin "1") (pinfunction "1_1") (pintype "passive"))
      (node (ref "R3.13") (pin "2") (pinfunction "2_2") (pintype "passive"))
      (node (ref "R3.13") (pin "3") (pinfunction "3_3") (pintype "passive"))
      (node (ref "R3.13") (pin "4") (pinfunction "4_4") (pintype "passive"))
      (node (ref "R3.13") (pin "5") (pinfunction "5_5") (pintype "passive"))
    )
    (net (code "53") (name "Net-(R3.14-Pad1)") (class "Default")
      (node (ref "R3.14") (pin "1") (pinfunction "1_1") (pintype "passive"))
      (node (ref "R3.14") (pin "2") (pinfunction "2_2") (pintype "passive"))
      (node (ref "R3.14") (pin "3") (pinfunction "3_3") (pintype "passive"))
      (node (ref "R3.14") (pin "4") (pinfunction "4_4") (pintype "passive"))
      (node (ref "R3.14") (pin "5") (pinfunction "5_5") (pintype "passive"))
    )
    (net (code "54") (name "Net-(R3.15-Pad1)") (class "Default")
      (node (ref "R3.15") (pin "1") (pinfunction "1_1") (pintype "passive"))
      (node (ref "R3.15") (pin "2") (pinfunction "2_2") (pintype "passive"))
      (node (ref "R3.15") (pin "3") (pinfunction "3_3") (pintype "passive"))
      (node (ref "R3.15") (pin "4") (pinfunction "4_4") (pintype "passive"))
      (node (ref "R3.15") (pin "5") (pinfunction "5_5") (pintype "passive"))
    )
    (net (code "55") (name "Net-(R3.16-Pad1)") (class "Default")
      (node (ref "R3.16") (pin "1") (pinfunction "1_1") (pintype "passive"))
      (node (ref "R3.16") (pin "2") (pinfunction "2_2") (pintype "passive"))
      (node (ref "R3.16") (pin "3") (pinfunction "3_3") (pintype "passive"))
      (node (ref "R3.16") (pin "4") (pinfunction "4_4") (pintype "passive"))
      (node (ref "R3.16") (pin "5") (pinfunction "5_5") (pintype "passive"))
    )
    (net (code "56") (name "Net-(R4.1-Pad1)") (class "Default")
      (node (ref "R4.1") (pin "1") (pinfunction "1_1") (pintype "passive"))
      (node (ref "R4.1") (pin "2") (pinfunction "2_2") (pintype "passive"))
      (node (ref "R4.1") (pin "3") (pinfunction "3_3") (pintype "passive"))
      (node (ref "R4.1") (pin "4") (pinfunction "4_4") (pintype "passive"))
      (node (ref "R4.1") (pin "5") (pinfunction "5_5") (pintype "passive"))
    )
    (net (code "57") (name "Net-(R4.2-Pad1)") (class "Default")
      (node (ref "R4.2") (pin "1") (pinfunction "1_1") (pintype "passive"))
      (node (ref "R4.2") (pin "2") (pinfunction "2_2") (pintype "passive"))
      (node (ref "R4.2") (pin "3") (pinfunction "3_3") (pintype "passive"))
      (node (ref "R4.2") (pin "4") (pinfunction "4_4") (pintype "passive"))
      (node (ref "R4.2") (pin "5") (pinfunction "5_5") (pintype "passive"))
    )
    (net (code "58") (name "Net-(R4.3-Pad1)") (class "Default")
      (node (ref "R4.3") (pin "1") (pinfunction "1_1") (pintype "passive"))
      (node (ref "R4.3") (pin "2") (pinfunction "2_2") (pintype "passive"))
      (node (ref "R4.3") (pin "3") (pinfunction "3_3") (pintype "passive"))
      (node (ref "R4.3") (pin "4") (pinfunction "4_4") (pintype "passive"))
      (node (ref "R4.3") (pin "5") (pinfunction "5_5") (pintype "passive"))
    )
    (net (code "59") (name "Net-(R4.4-Pad1)") (class "Default")
      (node (ref "R4.4") (pin "1") (pinfunction "1_1") (pintype "passive"))
      (node (ref "R4.4") (pin "2") (pinfunction "2_2") (pintype "passive"))
      (node (ref "R4.4") (pin "3") (pinfunction "3_3") (pintype "passive"))
      (node (ref "R4.4") (pin "4") (pinfunction "4_4") (pintype "passive"))
      (node (ref "R4.4") (pin "5") (pinfunction "5_5") (pintype "passive"))
    )
    (net (code "60") (name "Net-(R4.5-Pad1)") (class "Default")
      (node (ref "R4.5") (pin "1") (pinfunction "1_1") (pintype "passive"))
      (node (ref "R4.5") (pin "2") (pinfunction "2_2") (pintype "passive"))
      (node (ref "R4.5") (pin "3") (pinfunction "3_3") (pintype "passive"))
      (node (ref "R4.5") (pin "4") (pinfunction "4_4") (pintype "passive"))
      (node (ref "R4.5") (pin "5") (pinfunction "5_5") (pintype "passive"))
    )
    (net (code "61") (name "Net-(R4.6-Pad1)") (class "Default")
      (node (ref "R4.6") (pin "1") (pinfunction "1_1") (pintype "passive"))
      (node (ref "R4.6") (pin "2") (pinfunction "2_2") (pintype "passive"))
      (node (ref "R4.6") (pin "3") (pinfunction "3_3") (pintype "passive"))
      (node (ref "R4.6") (pin "4") (pinfunction "4_4") (pintype "passive"))
      (node (ref "R4.6") (pin "5") (pinfunction "5_5") (pintype "passive"))
    )
    (net (code "62") (name "Net-(R4.7-Pad1)") (class "Default")
      (node (ref "R4.7") (pin "1") (pinfunction "1_1") (pintype "passive"))
      (node (ref "R4.7") (pin "2") (pinfunction "2_2") (pintype "passive"))
      (node (ref "R4.7") (pin "3") (pinfunction "3_3") (pintype "passive"))
      (node (ref "R4.7") (pin "4") (pinfunction "4_4") (pintype "passive"))
      (node (ref "R4.7") (pin "5") (pinfunction "5_5") (pintype "passive"))
    )
    (net (code "63") (name "Net-(R4.8-Pad1)") (class "Default")
      (node (ref "R4.8") (pin "1") (pinfunction "1_1") (pintype "passive"))
      (node (ref "R4.8") (pin "2") (pinfunction "2_2") (pintype "passive"))
      (node (ref "R4.8") (pin "3") (pinfunction "3_3") (pintype "passive"))
      (node (ref "R4.8") (pin "4") (pinfunction "4_4") (pintype "passive"))
      (node (ref "R4.8") (pin "5") (pinfunction "5_5") (pintype "passive"))
    )
    (net (code "64") (name "Net-(R4.9-Pad1)") (class "Default")
      (node (ref "R4.9") (pin "1") (pinfunction "1_1") (pintype "passive"))
      (node (ref "R4.9") (pin "2") (pinfunction "2_2") (pintype "passive"))
      (node (ref "R4.9") (pin "3") (pinfunction "3_3") (pintype "passive"))
      (node (ref "R4.9") (pin "4") (pinfunction "4_4") (pintype "passive"))
      (node (ref "R4.9") (pin "5") (pinfunction "5_5") (pintype "passive"))
    )
    (net (code "65") (name "Net-(R4.10-Pad1)") (class "Default")
      (node (ref "R4.10") (pin "1") (pinfunction "1_1") (pintype "passive"))
      (node (ref "R4.10") (pin "2") (pinfunction "2_2") (pintype "passive"))
      (node (ref "R4.10") (pin "3") (pinfunction "3_3") (pintype "passive"))
      (node (ref "R4.10") (pin "4") (pinfunction "4_4") (pintype "passive"))
      (node (ref "R4.10") (pin "5") (pinfunction "5_5") (pintype "passive"))
    )
    (net (code "66") (name "Net-(R4.11-Pad1)") (class "Default")
      (node (ref "R4.11") (pin "1") (pinfunction "1_1") (pintype "passive"))
      (node (ref "R4.11") (pin "2") (pinfunction "2_2") (pintype "passive"))
      (node (ref "R4.11") (pin "3") (pinfunction "3_3") (pintype "passive"))
      (node (ref "R4.11") (pin "4") (pinfunction "4_4") (pintype "passive"))
      (node (ref "R4.11") (pin "5") (pinfunction "5_5") (pintype "passive"))
    )
    (net (code "67") (name "Net-(R4.12-Pad1)") (class "Default")
      (node (ref "R4.12") (pin "1") (pinfunction "1_1") (pintype "passive"))
      (node (ref "R4.12") (pin "2") (pinfunction "2_2") (pintype "passive"))
      (node (ref "R4.12") (pin "3") (pinfunction "3_3") (pintype "passive"))
      (node (ref "R4.12") (pin "4") (pinfunction "4_4") (pintype "passive"))
      (node (ref "R4.12") (pin "5") (pinfunction "5_5") (pintype "passive"))
    )
    (net (code "68") (name "Net-(R4.13-Pad1)") (class "Default")
      (node (ref "R4.13") (pin "1") (pinfunction "1_1") (pintype "passive"))
      (node (ref "R4.13") (pin "2") (pinfunction "2_2") (pintype "passive"))
      (node (ref "R4.13") (pin "3") (pinfunction "3_3") (pintype "passive"))
      (node (ref "R4.13") (pin "4") (pinfunction "4_4") (pintype "passive"))
      (node (ref "R4.13") (pin "5") (pinfunction "5_5") (pintype "passive"))
    )
    (net (code "69") (name "Net-(R4.14-Pad1)") (class "Default")
      (node (ref "R4.14") (pin "1") (pinfunction "1_1") (pintype "passive"))
      (node (ref "R4.14") (pin "2") (pinfunction "2_2") (pintype "passive"))
      (node (ref "R4.14") (pin "3") (pinfunction "3_3") (pintype "passive"))
      (node (ref "R4.14") (pin "4") (pinfunction "4_4") (pintype "passive"))
      (node (ref "R4.14") (pin "5") (pinfunction "5_5") (pintype "passive"))
    )
    (net (code "70") (name "Net-(R4.15-Pad1)") (class "Default")
      (node (ref "R4.15") (pin "1") (pinfunction "1_1") (pintype "passive"))
      (node (ref "R4.15") (pin "2") (pinfunction "2_2") (pintype "passive"))
      (node (ref "R4.15") (pin "3") (pinfunction "3_3") (pintype "passive"))
      (node (ref "R4.15") (pin "4") (pinfunction "4_4") (pintype "passive"))
      (node (ref "R4.15") (pin "5") (pinfunction "5_5") (pintype "passive"))
    )
    (net (code "71") (name "Net-(R4.16-Pad1)") (class "Default")
      (node (ref "R4.16") (pin "1") (pinfunction "1_1") (pintype "passive"))
      (node (ref "R4.16") (pin "2") (pinfunction "2_2") (pintype "passive"))
      (node (ref "R4.16") (pin "3") (pinfunction "3_3") (pintype "passive"))
      (node (ref "R4.16") (pin "4") (pinfunction "4_4") (pintype "passive"))
      (node (ref "R4.16") (pin "5") (pinfunction "5_5") (pintype "passive"))
    )
    (net (code "72") (name "Net-(SJ1-Pad1)") (class "Default")
      (node (ref "SJ1") (pin "1") (pinfunction "1_1") (pintype "passive"))
      (node (ref "SJ2") (pin "1") (pinfunction "1_1") (pintype "passive"))
      (node (ref "SJ3") (pin "2") (pinfunction "2_2") (pintype "passive"))
    )
    (net (code "73") (name "Net-(SJ7-Pad1)") (class "Default")
      (node (ref "SJ7") (pin "1") (pinfunction "1_1") (pintype "passive"))
      (node (ref "SJ8") (pin "1") (pinfunction "1_1") (pintype "passive"))
      (node (ref "SJ9") (pin "2") (pinfunction "2_2") (pintype "passive"))
    )
    (net (code "74") (name "Net-(U$3-VBUS)") (class "Default")
      (node (ref "CON1") (pin "4") (pinfunction "4_4") (pintype "bidirectional"))
      (node (ref "U$3") (pin "VUSB") (pinfunction "VBUS_VUSB") (pintype "bidirectional"))
    )
    (net (code "75") (name "Net-(U$4-CENTER)") (class "Default")
      (node (ref "CON-1") (pin "1") (pinfunction "1_1") (pintype "bidirectional"))
      (node (ref "U$4") (pin "P$4") (pinfunction "CENTER_P$4") (pintype "bidirectional"))
    )
    (net (code "76") (name "Net-(U$4-OUTER)") (class "Default")
      (node (ref "CON-1") (pin "3") (pinfunction "3_3") (pintype "bidirectional"))
      (node (ref "U$4") (pin "P$3") (pinfunction "OUTER_P$3") (pintype "bidirectional"))
    )
    (net (code "77") (name "Net-(U$4-SWITCH)") (class "Default")
      (node (ref "CON-1") (pin "2") (pinfunction "2_2") (pintype "bidirectional"))
      (node (ref "U$4") (pin "P$2") (pinfunction "SWITCH_P$2") (pintype "bidirectional"))
    )
    (net (code "78") (name "TOP-1") (class "Default")
      (node (ref "SJ9") (pin "1") (pinfunction "1_1") (pintype "passive"))
      (node (ref "TOP-1") (pin "1") (pinfunction "1_1") (pintype "passive"))
      (node (ref "TOP-1") (pin "11") (pinfunction "11_11") (pintype "passive"))
      (node (ref "TOP-1") (pin "13") (pinfunction "13_13") (pintype "passive"))
      (node (ref "TOP-1") (pin "15") (pinfunction "15_15") (pintype "passive"))
      (node (ref "TOP-1") (pin "17") (pinfunction "17_17") (pintype "passive"))
      (node (ref "TOP-1") (pin "19") (pinfunction "19_19") (pintype "passive"))
      (node (ref "TOP-1") (pin "21") (pinfunction "21_21") (pintype "passive"))
      (node (ref "TOP-1") (pin "23") (pinfunction "23_23") (pintype "passive"))
      (node (ref "TOP-1") (pin "25") (pinfunction "25_25") (pintype "passive"))
      (node (ref "TOP-1") (pin "27") (pinfunction "27_27") (pintype "passive"))
      (node (ref "TOP-1") (pin "29") (pinfunction "29_29") (pintype "passive"))
      (node (ref "TOP-1") (pin "3") (pinfunction "3_3") (pintype "passive"))
      (node (ref "TOP-1") (pin "31") (pinfunction "31_31") (pintype "passive"))
      (node (ref "TOP-1") (pin "5") (pinfunction "5_5") (pintype "passive"))
      (node (ref "TOP-1") (pin "7") (pinfunction "7_7") (pintype "passive"))
      (node (ref "TOP-1") (pin "9") (pinfunction "9_9") (pintype "passive"))
      (node (ref "TOP-2") (pin "2") (pinfunction "2_2") (pintype "passive"))
      (node (ref "TOP-3") (pin "1") (pinfunction "1_1") (pintype "passive"))
      (node (ref "TOP-3") (pin "11") (pinfunction "11_11") (pintype "passive"))
      (node (ref "TOP-3") (pin "13") (pinfunction "13_13") (pintype "passive"))
      (node (ref "TOP-3") (pin "15") (pinfunction "15_15") (pintype "passive"))
      (node (ref "TOP-3") (pin "17") (pinfunction "17_17") (pintype "passive"))
      (node (ref "TOP-3") (pin "19") (pinfunction "19_19") (pintype "passive"))
      (node (ref "TOP-3") (pin "21") (pinfunction "21_21") (pintype "passive"))
      (node (ref "TOP-3") (pin "23") (pinfunction "23_23") (pintype "passive"))
      (node (ref "TOP-3") (pin "25") (pinfunction "25_25") (pintype "passive"))
      (node (ref "TOP-3") (pin "27") (pinfunction "27_27") (pintype "passive"))
      (node (ref "TOP-3") (pin "29") (pinfunction "29_29") (pintype "passive"))
      (node (ref "TOP-3") (pin "3") (pinfunction "3_3") (pintype "passive"))
      (node (ref "TOP-3") (pin "31") (pinfunction "31_31") (pintype "passive"))
      (node (ref "TOP-3") (pin "5") (pinfunction "5_5") (pintype "passive"))
      (node (ref "TOP-3") (pin "7") (pinfunction "7_7") (pintype "passive"))
      (node (ref "TOP-3") (pin "9") (pinfunction "9_9") (pintype "passive"))
    )
    (net (code "79") (name "TOP-2") (class "Default")
      (node (ref "SJ3") (pin "1") (pinfunction "1_1") (pintype "passive"))
      (node (ref "TOP-1") (pin "10") (pinfunction "10_10") (pintype "passive"))
      (node (ref "TOP-1") (pin "12") (pinfunction "12_12") (pintype "passive"))
      (node (ref "TOP-1") (pin "14") (pinfunction "14_14") (pintype "passive"))
      (node (ref "TOP-1") (pin "16") (pinfunction "16_16") (pintype "passive"))
      (node (ref "TOP-1") (pin "18") (pinfunction "18_18") (pintype "passive"))
      (node (ref "TOP-1") (pin "2") (pinfunction "2_2") (pintype "passive"))
      (node (ref "TOP-1") (pin "20") (pinfunction "20_20") (pintype "passive"))
      (node (ref "TOP-1") (pin "22") (pinfunction "22_22") (pintype "passive"))
      (node (ref "TOP-1") (pin "24") (pinfunction "24_24") (pintype "passive"))
      (node (ref "TOP-1") (pin "26") (pinfunction "26_26") (pintype "passive"))
      (node (ref "TOP-1") (pin "28") (pinfunction "28_28") (pintype "passive"))
      (node (ref "TOP-1") (pin "30") (pinfunction "30_30") (pintype "passive"))
      (node (ref "TOP-1") (pin "32") (pinfunction "32_32") (pintype "passive"))
      (node (ref "TOP-1") (pin "4") (pinfunction "4_4") (pintype "passive"))
      (node (ref "TOP-1") (pin "6") (pinfunction "6_6") (pintype "passive"))
      (node (ref "TOP-1") (pin "8") (pinfunction "8_8") (pintype "passive"))
      (node (ref "TOP-2") (pin "1") (pinfunction "1_1") (pintype "passive"))
      (node (ref "TOP-3") (pin "10") (pinfunction "10_10") (pintype "passive"))
      (node (ref "TOP-3") (pin "12") (pinfunction "12_12") (pintype "passive"))
      (node (ref "TOP-3") (pin "14") (pinfunction "14_14") (pintype "passive"))
      (node (ref "TOP-3") (pin "16") (pinfunction "16_16") (pintype "passive"))
      (node (ref "TOP-3") (pin "18") (pinfunction "18_18") (pintype "passive"))
      (node (ref "TOP-3") (pin "2") (pinfunction "2_2") (pintype "passive"))
      (node (ref "TOP-3") (pin "20") (pinfunction "20_20") (pintype "passive"))
      (node (ref "TOP-3") (pin "22") (pinfunction "22_22") (pintype "passive"))
      (node (ref "TOP-3") (pin "24") (pinfunction "24_24") (pintype "passive"))
      (node (ref "TOP-3") (pin "26") (pinfunction "26_26") (pintype "passive"))
      (node (ref "TOP-3") (pin "28") (pinfunction "28_28") (pintype "passive"))
      (node (ref "TOP-3") (pin "30") (pinfunction "30_30") (pintype "passive"))
      (node (ref "TOP-3") (pin "32") (pinfunction "32_32") (pintype "passive"))
      (node (ref "TOP-3") (pin "4") (pinfunction "4_4") (pintype "passive"))
      (node (ref "TOP-3") (pin "6") (pinfunction "6_6") (pintype "passive"))
      (node (ref "TOP-3") (pin "8") (pinfunction "8_8") (pintype "passive"))
    )
  )
)
